# MiniToyRobot.net
KiCad netlist of a schematic drawn in Altium Designer
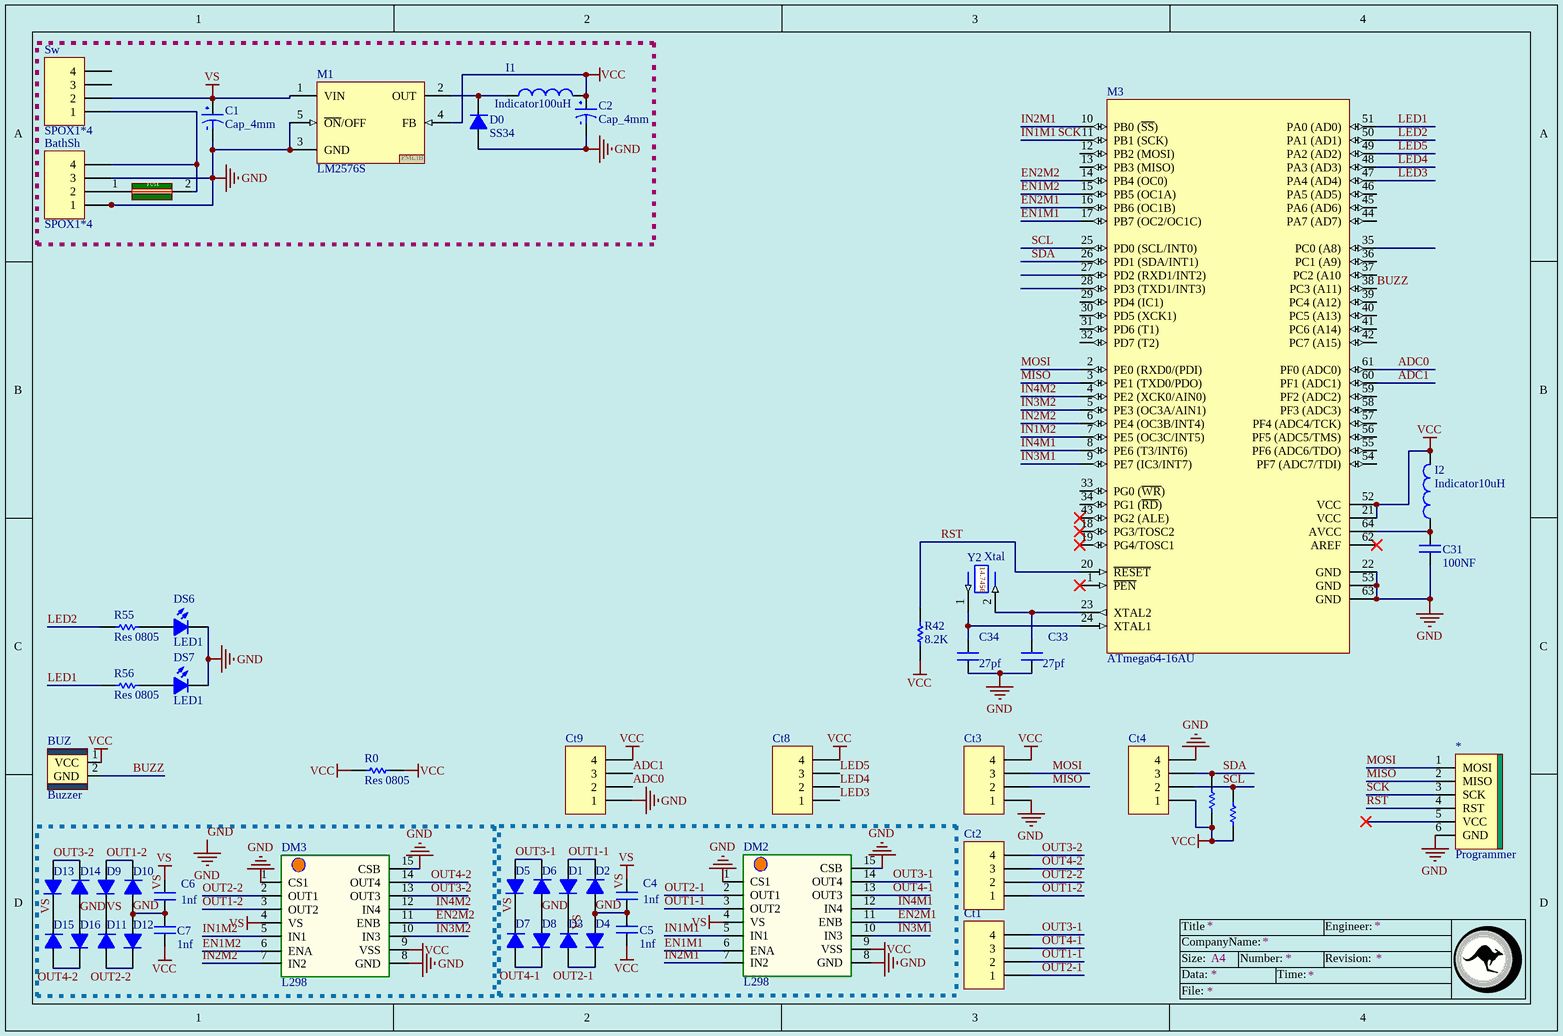
[diagram p0: MiniToyRobot.SchDoc]

(export (version "E")
  (design (tool "Eeschema 10.0.6"))
  (components
    (comp (ref "*")
      (value "Programmer")
      (footprint "Programmer")
      (libsource (lib "PMLIB") (part "Programmer"))
    )
    (comp (ref "BathSh")
      (value "SPOX1*4")
      (footprint "SPOX_1*4RIGHT")
      (libsource (lib "PMLIB") (part "SPOX1*4"))
    )
    (comp (ref "BUZ") (value "Buzzer") (footprint "Buzzer") (libsource (lib "PMLIB") (part "Buzzer")))
    (comp (ref "C1") (value "Cap_4mm") (footprint "Cap_4mm") (libsource (lib "PMLIB") (part "Cap_Pola")))
    (comp (ref "C2") (value "Cap_4mm") (footprint "Cap_4mm") (libsource (lib "PMLIB") (part "Cap_Pola")))
    (comp (ref "C4")
      (value "1nf")
      (footprint "Cap0805")
      (description "surface mount capacitor (size 805)")
      (libsource (lib "PMLIB") (part "Cap0805"))
    )
    (comp (ref "C5")
      (value "1nf")
      (footprint "Cap0805")
      (description "surface mount capacitor (size 805)")
      (libsource (lib "PMLIB") (part "Cap0805"))
    )
    (comp (ref "C6")
      (value "1nf")
      (footprint "Cap0805")
      (description "surface mount capacitor (size 805)")
      (libsource (lib "PMLIB") (part "Cap0805"))
    )
    (comp (ref "C7")
      (value "1nf")
      (footprint "Cap0805")
      (description "surface mount capacitor (size 805)")
      (libsource (lib "PMLIB") (part "Cap0805"))
    )
    (comp (ref "C31")
      (value "100NF")
      (footprint "Cap0805")
      (description "surface mount capacitor (size 805)")
      (libsource (lib "PMLIB") (part "Cap0805"))
    )
    (comp (ref "C33")
      (value "27pf")
      (footprint "Cap0805")
      (description "surface mount capacitor (size 805)")
      (libsource (lib "PMLIB") (part "Cap0805"))
    )
    (comp (ref "C34")
      (value "27pf")
      (footprint "Cap0805")
      (description "surface mount capacitor (size 805)")
      (libsource (lib "PMLIB") (part "Cap0805"))
    )
    (comp (ref "Ct1")
      (value "SPOX1*4")
      (footprint "SPOX_1*4RIGHT")
      (libsource (lib "PMLIB") (part "SPOX1*4"))
    )
    (comp (ref "Ct2")
      (value "SPOX1*4")
      (footprint "SPOX_1*4RIGHT")
      (libsource (lib "PMLIB") (part "SPOX1*4"))
    )
    (comp (ref "Ct3")
      (value "SPOX1*4")
      (footprint "SPOX_1*4RIGHT")
      (libsource (lib "PMLIB") (part "SPOX1*4"))
    )
    (comp (ref "Ct4")
      (value "SPOX1*4")
      (footprint "SPOX_1*4RIGHT")
      (libsource (lib "PMLIB") (part "SPOX1*4"))
    )
    (comp (ref "Ct8")
      (value "SPOX1*4")
      (footprint "SPOX_1*4RIGHT")
      (libsource (lib "PMLIB") (part "SPOX1*4"))
    )
    (comp (ref "Ct9")
      (value "SPOX1*4")
      (footprint "SPOX_1*4RIGHT")
      (libsource (lib "PMLIB") (part "SPOX1*4"))
    )
    (comp (ref "D0") (value "SS34") (footprint "Diod-1A-SMD") (libsource (lib "PMLIB") (part "Diode")))
    (comp (ref "D1") (value "SS14") (footprint "Diod-1A-SMD") (libsource (lib "PMLIB") (part "Diode")))
    (comp (ref "D2") (value "SS14") (footprint "Diod-1A-SMD") (libsource (lib "PMLIB") (part "Diode")))
    (comp (ref "D3") (value "SS14") (footprint "Diod-1A-SMD") (libsource (lib "PMLIB") (part "Diode")))
    (comp (ref "D4") (value "SS14") (footprint "Diod-1A-SMD") (libsource (lib "PMLIB") (part "Diode")))
    (comp (ref "D5") (value "SS14") (footprint "Diod-1A-SMD") (libsource (lib "PMLIB") (part "Diode")))
    (comp (ref "D6") (value "SS14") (footprint "Diod-1A-SMD") (libsource (lib "PMLIB") (part "Diode")))
    (comp (ref "D7") (value "SS14") (footprint "Diod-1A-SMD") (libsource (lib "PMLIB") (part "Diode")))
    (comp (ref "D8") (value "SS14") (footprint "Diod-1A-SMD") (libsource (lib "PMLIB") (part "Diode")))
    (comp (ref "D9") (value "SS14") (footprint "Diod-1A-SMD") (libsource (lib "PMLIB") (part "Diode")))
    (comp (ref "D10") (value "SS14") (footprint "Diod-1A-SMD") (libsource (lib "PMLIB") (part "Diode")))
    (comp (ref "D11") (value "SS14") (footprint "Diod-1A-SMD") (libsource (lib "PMLIB") (part "Diode")))
    (comp (ref "D12") (value "SS14") (footprint "Diod-1A-SMD") (libsource (lib "PMLIB") (part "Diode")))
    (comp (ref "D13") (value "SS14") (footprint "Diod-1A-SMD") (libsource (lib "PMLIB") (part "Diode")))
    (comp (ref "D14") (value "SS14") (footprint "Diod-1A-SMD") (libsource (lib "PMLIB") (part "Diode")))
    (comp (ref "D15") (value "SS14") (footprint "Diod-1A-SMD") (libsource (lib "PMLIB") (part "Diode")))
    (comp (ref "D16") (value "SS14") (footprint "Diod-1A-SMD") (libsource (lib "PMLIB") (part "Diode")))
    (comp (ref "DM2") (value "L298") (footprint "L298") (libsource (lib "PMLIB") (part "L298")))
    (comp (ref "DM3") (value "L298") (footprint "L298") (libsource (lib "PMLIB") (part "L298")))
    (comp (ref "DS6") (value "LED1") (footprint "LED_SMD0805RED") (libsource (lib "PMLIB") (part "LED1")))
    (comp (ref "DS7") (value "LED1") (footprint "LED_SMD0805RED") (libsource (lib "PMLIB") (part "LED1")))
    (comp (ref "Fuse") (value "fuse3") (footprint "fuse_SMD0805") (libsource (lib "PMLIB") (part "fuse3")))
    (comp (ref "I1")
      (value "Indicator100uH")
      (footprint "Indicator_SMD")
      (libsource (lib "PMLIB") (part "Indicator100uH"))
    )
    (comp (ref "I2")
      (value "Indicator10uH")
      (footprint "1206")
      (libsource (lib "PMLIB") (part "Indicator100uH"))
    )
    (comp (ref "M1") (value "LM2576S") (footprint "LM2576S") (libsource (lib "PMLIB") (part "LM2576S")))
    (comp (ref "M3")
      (value "ATmega64-16AU")
      (footprint "64A_N")
      (libsource (lib "Atmel Microcontroller megaAVR") (part "ATmega64-16AU"))
    )
    (comp (ref "R0") (value "Res 0805") (footprint "1206") (libsource (lib "PMLIB") (part "Res 0805")))
    (comp (ref "R42") (value "8.2K") (footprint "R0805") (libsource (lib "PMLIB") (part "Res 0805")))
    (comp (ref "R55") (value "Res 0805") (footprint "R0805") (libsource (lib "PMLIB") (part "Res 0805")))
    (comp (ref "R56") (value "Res 0805") (footprint "R0805") (libsource (lib "PMLIB") (part "Res 0805")))
    (comp (ref "RD1") (value "Res 0805") (footprint "R0805") (libsource (lib "PMLIB") (part "Res 0805")))
    (comp (ref "RD2") (value "Res 0805") (footprint "R0805") (libsource (lib "PMLIB") (part "Res 0805")))
    (comp (ref "Sw") (value "SPOX1*4") (footprint "SPOX_1*4RIGHT") (libsource (lib "PMLIB") (part "SPOX1*4")))
    (comp (ref "Y2") (value "Xtal") (footprint "Crystal") (libsource (lib "PMLIB") (part "Crystal")))
  )
  (nets
    (net (code "1") (name "/ADC0") (class "Default")
      (node (ref "Ct9") (pin "2") (pinfunction "2_2") (pintype "passive"))
      (node (ref "M3") (pin "61") (pinfunction "PF0_(ADC0)_61") (pintype "bidirectional"))
    )
    (net (code "2") (name "/ADC1") (class "Default")
      (node (ref "Ct9") (pin "3") (pinfunction "3_3") (pintype "passive"))
      (node (ref "M3") (pin "60") (pinfunction "PF1_(ADC1)_60") (pintype "bidirectional"))
    )
    (net (code "3") (name "/BUZZ") (class "Default")
      (node (ref "BUZ") (pin "2") (pinfunction "GND_2") (pintype "passive"))
      (node (ref "M3") (pin "38") (pinfunction "PC3_(A11)_38") (pintype "bidirectional"))
    )
    (net (code "4") (name "/EN1M1") (class "Default")
      (node (ref "DM2") (pin "6") (pinfunction "ENA_6") (pintype "passive"))
      (node (ref "M3") (pin "17") (pinfunction "PB7_(OC2/OC1C)_17") (pintype "bidirectional"))
    )
    (net (code "5") (name "/EN1M2") (class "Default")
      (node (ref "DM3") (pin "6") (pinfunction "ENA_6") (pintype "passive"))
      (node (ref "M3") (pin "15") (pinfunction "PB5_(OC1A)_15") (pintype "bidirectional"))
    )
    (net (code "6") (name "/EN2M1") (class "Default")
      (node (ref "DM2") (pin "11") (pinfunction "ENB_11") (pintype "passive"))
      (node (ref "M3") (pin "16") (pinfunction "PB6_(OC1B)_16") (pintype "bidirectional"))
    )
    (net (code "7") (name "/EN2M2") (class "Default")
      (node (ref "DM3") (pin "11") (pinfunction "ENB_11") (pintype "passive"))
      (node (ref "M3") (pin "14") (pinfunction "PB4_(OC0)_14") (pintype "bidirectional"))
    )
    (net (code "8") (name "/IN1M1") (class "Default")
      (node (ref "*") (pin "3") (pinfunction "SCK_3") (pintype "passive"))
      (node (ref "DM2") (pin "5") (pinfunction "IN1_5") (pintype "passive"))
      (node (ref "M3") (pin "11") (pinfunction "PB1_(SCK)_11") (pintype "bidirectional"))
    )
    (net (code "9") (name "/IN1M2") (class "Default")
      (node (ref "DM3") (pin "5") (pinfunction "IN1_5") (pintype "passive"))
      (node (ref "M3") (pin "7") (pinfunction "PE5_(OC3C/INT5)_7") (pintype "bidirectional"))
    )
    (net (code "10") (name "/IN2M1") (class "Default")
      (node (ref "DM2") (pin "7") (pinfunction "IN2_7") (pintype "passive"))
      (node (ref "M3") (pin "10") (pinfunction "PB0_(~{SS})_10") (pintype "bidirectional"))
    )
    (net (code "11") (name "/IN2M2") (class "Default")
      (node (ref "DM3") (pin "7") (pinfunction "IN2_7") (pintype "passive"))
      (node (ref "M3") (pin "6") (pinfunction "PE4_(OC3B/INT4)_6") (pintype "bidirectional"))
    )
    (net (code "12") (name "/IN3M1") (class "Default")
      (node (ref "DM2") (pin "10") (pinfunction "IN3_10") (pintype "passive"))
      (node (ref "M3") (pin "9") (pinfunction "PE7_(IC3/INT7)_9") (pintype "bidirectional"))
    )
    (net (code "13") (name "/IN3M2") (class "Default")
      (node (ref "DM3") (pin "10") (pinfunction "IN3_10") (pintype "passive"))
      (node (ref "M3") (pin "5") (pinfunction "PE3_(OC3A/AIN1)_5") (pintype "bidirectional"))
    )
    (net (code "14") (name "/IN4M1") (class "Default")
      (node (ref "DM2") (pin "12") (pinfunction "IN4_12") (pintype "passive"))
      (node (ref "M3") (pin "8") (pinfunction "PE6_(T3/INT6)_8") (pintype "bidirectional"))
    )
    (net (code "15") (name "/IN4M2") (class "Default")
      (node (ref "DM3") (pin "12") (pinfunction "IN4_12") (pintype "passive"))
      (node (ref "M3") (pin "4") (pinfunction "PE2_(XCK0/AIN0)_4") (pintype "bidirectional"))
    )
    (net (code "16") (name "/LED1") (class "Default")
      (node (ref "M3") (pin "51") (pinfunction "PA0_(AD0)_51") (pintype "bidirectional"))
      (node (ref "R56") (pin "2") (pinfunction "2_2") (pintype "passive"))
    )
    (net (code "17") (name "/LED2") (class "Default")
      (node (ref "M3") (pin "50") (pinfunction "PA1_(AD1)_50") (pintype "bidirectional"))
      (node (ref "R55") (pin "2") (pinfunction "2_2") (pintype "passive"))
    )
    (net (code "18") (name "/LED3") (class "Default")
      (node (ref "Ct8") (pin "1") (pinfunction "1_1") (pintype "passive"))
      (node (ref "M3") (pin "47") (pinfunction "PA4_(AD4)_47") (pintype "bidirectional"))
    )
    (net (code "19") (name "/LED4") (class "Default")
      (node (ref "Ct8") (pin "2") (pinfunction "2_2") (pintype "passive"))
      (node (ref "M3") (pin "48") (pinfunction "PA3_(AD3)_48") (pintype "bidirectional"))
    )
    (net (code "20") (name "/LED5") (class "Default")
      (node (ref "Ct8") (pin "3") (pinfunction "3_3") (pintype "passive"))
      (node (ref "M3") (pin "49") (pinfunction "PA2_(AD2)_49") (pintype "bidirectional"))
    )
    (net (code "21") (name "/MISO") (class "Default")
      (node (ref "*") (pin "2") (pinfunction "MISO_2") (pintype "passive"))
      (node (ref "Ct3") (pin "2") (pinfunction "2_2") (pintype "passive"))
      (node (ref "M3") (pin "3") (pinfunction "PE1_(TXD0/PDO)_3") (pintype "bidirectional"))
    )
    (net (code "22") (name "/MOSI") (class "Default")
      (node (ref "*") (pin "1") (pinfunction "MOSI_1") (pintype "passive"))
      (node (ref "Ct3") (pin "3") (pinfunction "3_3") (pintype "passive"))
      (node (ref "M3") (pin "2") (pinfunction "PE0_(RXD0/(PDI)_2") (pintype "bidirectional"))
    )
    (net (code "23") (name "/OUT1-1") (class "Default")
      (node (ref "Ct1") (pin "2") (pinfunction "2_2") (pintype "passive"))
      (node (ref "D1") (pin "A") (pinfunction "A_A") (pintype "passive"))
      (node (ref "D2") (pin "K") (pinfunction "K_K") (pintype "passive"))
      (node (ref "DM2") (pin "3") (pinfunction "OUT2_3") (pintype "passive"))
    )
    (net (code "24") (name "/OUT1-2") (class "Default")
      (node (ref "Ct2") (pin "1") (pinfunction "1_1") (pintype "passive"))
      (node (ref "D10") (pin "K") (pinfunction "K_K") (pintype "passive"))
      (node (ref "D9") (pin "A") (pinfunction "A_A") (pintype "passive"))
      (node (ref "DM3") (pin "3") (pinfunction "OUT2_3") (pintype "passive"))
    )
    (net (code "25") (name "/OUT2-1") (class "Default")
      (node (ref "Ct1") (pin "1") (pinfunction "1_1") (pintype "passive"))
      (node (ref "D3") (pin "A") (pinfunction "A_A") (pintype "passive"))
      (node (ref "D4") (pin "K") (pinfunction "K_K") (pintype "passive"))
      (node (ref "DM2") (pin "2") (pinfunction "OUT1_2") (pintype "passive"))
    )
    (net (code "26") (name "/OUT2-2") (class "Default")
      (node (ref "Ct2") (pin "2") (pinfunction "2_2") (pintype "passive"))
      (node (ref "D11") (pin "A") (pinfunction "A_A") (pintype "passive"))
      (node (ref "D12") (pin "K") (pinfunction "K_K") (pintype "passive"))
      (node (ref "DM3") (pin "2") (pinfunction "OUT1_2") (pintype "passive"))
    )
    (net (code "27") (name "/OUT3-1") (class "Default")
      (node (ref "Ct1") (pin "4") (pinfunction "4_4") (pintype "passive"))
      (node (ref "D5") (pin "A") (pinfunction "A_A") (pintype "passive"))
      (node (ref "D6") (pin "K") (pinfunction "K_K") (pintype "passive"))
      (node (ref "DM2") (pin "14") (pinfunction "OUT4_14") (pintype "passive"))
    )
    (net (code "28") (name "/OUT3-2") (class "Default")
      (node (ref "Ct2") (pin "4") (pinfunction "4_4") (pintype "passive"))
      (node (ref "D13") (pin "A") (pinfunction "A_A") (pintype "passive"))
      (node (ref "D14") (pin "K") (pinfunction "K_K") (pintype "passive"))
      (node (ref "DM3") (pin "13") (pinfunction "OUT3_13") (pintype "passive"))
    )
    (net (code "29") (name "/OUT4-1") (class "Default")
      (node (ref "Ct1") (pin "3") (pinfunction "3_3") (pintype "passive"))
      (node (ref "D7") (pin "A") (pinfunction "A_A") (pintype "passive"))
      (node (ref "D8") (pin "K") (pinfunction "K_K") (pintype "passive"))
      (node (ref "DM2") (pin "13") (pinfunction "OUT3_13") (pintype "passive"))
    )
    (net (code "30") (name "/OUT4-2") (class "Default")
      (node (ref "Ct2") (pin "3") (pinfunction "3_3") (pintype "passive"))
      (node (ref "D15") (pin "A") (pinfunction "A_A") (pintype "passive"))
      (node (ref "D16") (pin "K") (pinfunction "K_K") (pintype "passive"))
      (node (ref "DM3") (pin "14") (pinfunction "OUT4_14") (pintype "passive"))
    )
    (net (code "31") (name "/RST") (class "Default")
      (node (ref "*") (pin "4") (pinfunction "RST_4") (pintype "passive"))
      (node (ref "M3") (pin "20") (pinfunction "~{RESET}_20") (pintype "input"))
      (node (ref "R42") (pin "1") (pinfunction "1_1") (pintype "passive"))
    )
    (net (code "32") (name "/SCL") (class "Default")
      (node (ref "Ct4") (pin "2") (pinfunction "2_2") (pintype "passive"))
      (node (ref "M3") (pin "25") (pinfunction "PD0_(SCL/INT0)_25") (pintype "bidirectional"))
      (node (ref "RD2") (pin "2") (pinfunction "2_2") (pintype "passive"))
    )
    (net (code "33") (name "/SDA") (class "Default")
      (node (ref "Ct4") (pin "3") (pinfunction "3_3") (pintype "passive"))
      (node (ref "M3") (pin "26") (pinfunction "PD1_(SDA/INT1)_26") (pintype "bidirectional"))
      (node (ref "RD1") (pin "2") (pinfunction "2_2") (pintype "passive"))
    )
    (net (code "34") (name "GND") (class "Default")
      (node (ref "*") (pin "6") (pinfunction "GND_6") (pintype "passive"))
      (node (ref "BathSh") (pin "1") (pinfunction "1_1") (pintype "passive"))
      (node (ref "BathSh") (pin "3") (pinfunction "3_3") (pintype "passive"))
      (node (ref "C1") (pin "1") (pinfunction "1_1") (pintype "passive"))
      (node (ref "C2") (pin "1") (pinfunction "1_1") (pintype "passive"))
      (node (ref "C31") (pin "1") (pinfunction "1_1") (pintype "passive"))
      (node (ref "C33") (pin "1") (pinfunction "1_1") (pintype "passive"))
      (node (ref "C34") (pin "1") (pinfunction "1_1") (pintype "passive"))
      (node (ref "C4") (pin "1") (pinfunction "1_1") (pintype "passive"))
      (node (ref "C5") (pin "2") (pinfunction "2_2") (pintype "passive"))
      (node (ref "C6") (pin "1") (pinfunction "1_1") (pintype "passive"))
      (node (ref "C7") (pin "2") (pinfunction "2_2") (pintype "passive"))
      (node (ref "Ct3") (pin "1") (pinfunction "1_1") (pintype "passive"))
      (node (ref "Ct4") (pin "4") (pinfunction "4_4") (pintype "passive"))
      (node (ref "Ct9") (pin "1") (pinfunction "1_1") (pintype "passive"))
      (node (ref "D0") (pin "A") (pinfunction "A_A") (pintype "passive"))
      (node (ref "D10") (pin "A") (pinfunction "A_A") (pintype "passive"))
      (node (ref "D12") (pin "A") (pinfunction "A_A") (pintype "passive"))
      (node (ref "D14") (pin "A") (pinfunction "A_A") (pintype "passive"))
      (node (ref "D16") (pin "A") (pinfunction "A_A") (pintype "passive"))
      (node (ref "D2") (pin "A") (pinfunction "A_A") (pintype "passive"))
      (node (ref "D4") (pin "A") (pinfunction "A_A") (pintype "passive"))
      (node (ref "D6") (pin "A") (pinfunction "A_A") (pintype "passive"))
      (node (ref "D8") (pin "A") (pinfunction "A_A") (pintype "passive"))
      (node (ref "DM2") (pin "1") (pinfunction "CS1_1") (pintype "passive"))
      (node (ref "DM2") (pin "15") (pinfunction "CSB_15") (pintype "passive"))
      (node (ref "DM2") (pin "8") (pinfunction "GND_8") (pintype "passive"))
      (node (ref "DM3") (pin "1") (pinfunction "CS1_1") (pintype "passive"))
      (node (ref "DM3") (pin "15") (pinfunction "CSB_15") (pintype "passive"))
      (node (ref "DM3") (pin "8") (pinfunction "GND_8") (pintype "passive"))
      (node (ref "DS6") (pin "K") (pinfunction "K_K") (pintype "passive"))
      (node (ref "DS7") (pin "K") (pinfunction "K_K") (pintype "passive"))
      (node (ref "M1") (pin "3") (pinfunction "GND_3") (pintype "power_in"))
      (node (ref "M1") (pin "5") (pinfunction "~{ON}/OFF_5") (pintype "input"))
      (node (ref "M3") (pin "22") (pinfunction "GND_22") (pintype "power_in"))
      (node (ref "M3") (pin "53") (pinfunction "GND_53") (pintype "power_in"))
      (node (ref "M3") (pin "63") (pinfunction "GND_63") (pintype "power_in"))
    )
    (net (code "35") (name "Net-(DS6-PadA)") (class "Default")
      (node (ref "DS6") (pin "A") (pinfunction "A_A") (pintype "passive"))
      (node (ref "R55") (pin "1") (pinfunction "1_1") (pintype "passive"))
    )
    (net (code "36") (name "Net-(DS7-PadA)") (class "Default")
      (node (ref "DS7") (pin "A") (pinfunction "A_A") (pintype "passive"))
      (node (ref "R56") (pin "1") (pinfunction "1_1") (pintype "passive"))
    )
    (net (code "37") (name "Net-(Fuse-IN)") (class "Default")
      (node (ref "BathSh") (pin "2") (pinfunction "2_2") (pintype "passive"))
      (node (ref "Fuse") (pin "1") (pinfunction "IN_1") (pintype "passive"))
    )
    (net (code "38") (name "Net-(Fuse-OUT)") (class "Default")
      (node (ref "BathSh") (pin "4") (pinfunction "4_4") (pintype "passive"))
      (node (ref "Fuse") (pin "2") (pinfunction "OUT_2") (pintype "passive"))
      (node (ref "Sw") (pin "1") (pinfunction "1_1") (pintype "passive"))
    )
    (net (code "39") (name "Net-(M1-OUT)") (class "Default")
      (node (ref "D0") (pin "K") (pinfunction "K_K") (pintype "passive"))
      (node (ref "I1") (pin "1") (pinfunction "1_1") (pintype "passive"))
      (node (ref "M1") (pin "2") (pinfunction "OUT_2") (pintype "power_in"))
    )
    (net (code "40") (name "Net-(M3-AVCC)") (class "Default")
      (node (ref "C31") (pin "2") (pinfunction "2_2") (pintype "passive"))
      (node (ref "I2") (pin "1") (pinfunction "1_1") (pintype "passive"))
      (node (ref "M3") (pin "64") (pinfunction "AVCC_64") (pintype "power_in"))
    )
    (net (code "41") (name "Net-(M3-XTAL1)") (class "Default")
      (node (ref "C34") (pin "2") (pinfunction "2_2") (pintype "passive"))
      (node (ref "M3") (pin "24") (pinfunction "XTAL1_24") (pintype "input"))
      (node (ref "Y2") (pin "1") (pinfunction "1_1") (pintype "output"))
    )
    (net (code "42") (name "Net-(M3-XTAL2)") (class "Default")
      (node (ref "C33") (pin "2") (pinfunction "2_2") (pintype "passive"))
      (node (ref "M3") (pin "23") (pinfunction "XTAL2_23") (pintype "output"))
      (node (ref "Y2") (pin "2") (pinfunction "2_2") (pintype "input"))
    )
    (net (code "43") (name "VCC") (class "Default")
      (node (ref "BUZ") (pin "1") (pinfunction "VCC_1") (pintype "passive"))
      (node (ref "C2") (pin "2") (pinfunction "2_2") (pintype "passive"))
      (node (ref "C5") (pin "1") (pinfunction "1_1") (pintype "passive"))
      (node (ref "C7") (pin "1") (pinfunction "1_1") (pintype "passive"))
      (node (ref "Ct3") (pin "4") (pinfunction "4_4") (pintype "passive"))
      (node (ref "Ct4") (pin "1") (pinfunction "1_1") (pintype "passive"))
      (node (ref "Ct8") (pin "4") (pinfunction "4_4") (pintype "passive"))
      (node (ref "Ct9") (pin "4") (pinfunction "4_4") (pintype "passive"))
      (node (ref "DM2") (pin "9") (pinfunction "VSS_9") (pintype "passive"))
      (node (ref "DM3") (pin "9") (pinfunction "VSS_9") (pintype "passive"))
      (node (ref "I1") (pin "2") (pinfunction "2_2") (pintype "passive"))
      (node (ref "I2") (pin "2") (pinfunction "2_2") (pintype "passive"))
      (node (ref "M1") (pin "4") (pinfunction "FB_4") (pintype "input"))
      (node (ref "M3") (pin "21") (pinfunction "VCC_21") (pintype "power_in"))
      (node (ref "M3") (pin "52") (pinfunction "VCC_52") (pintype "power_in"))
      (node (ref "R0") (pin "1") (pinfunction "1_1") (pintype "passive"))
      (node (ref "R0") (pin "2") (pinfunction "2_2") (pintype "passive"))
      (node (ref "R42") (pin "2") (pinfunction "2_2") (pintype "passive"))
      (node (ref "RD1") (pin "1") (pinfunction "1_1") (pintype "passive"))
      (node (ref "RD2") (pin "1") (pinfunction "1_1") (pintype "passive"))
    )
    (net (code "44") (name "VS") (class "Default")
      (node (ref "C1") (pin "2") (pinfunction "2_2") (pintype "passive"))
      (node (ref "C4") (pin "2") (pinfunction "2_2") (pintype "passive"))
      (node (ref "C6") (pin "2") (pinfunction "2_2") (pintype "passive"))
      (node (ref "D1") (pin "K") (pinfunction "K_K") (pintype "passive"))
      (node (ref "D11") (pin "K") (pinfunction "K_K") (pintype "passive"))
      (node (ref "D13") (pin "K") (pinfunction "K_K") (pintype "passive"))
      (node (ref "D15") (pin "K") (pinfunction "K_K") (pintype "passive"))
      (node (ref "D3") (pin "K") (pinfunction "K_K") (pintype "passive"))
      (node (ref "D5") (pin "K") (pinfunction "K_K") (pintype "passive"))
      (node (ref "D7") (pin "K") (pinfunction "K_K") (pintype "passive"))
      (node (ref "D9") (pin "K") (pinfunction "K_K") (pintype "passive"))
      (node (ref "DM2") (pin "4") (pinfunction "VS_4") (pintype "passive"))
      (node (ref "DM3") (pin "4") (pinfunction "VS_4") (pintype "passive"))
      (node (ref "M1") (pin "1") (pinfunction "VIN_1") (pintype "power_in"))
      (node (ref "Sw") (pin "2") (pinfunction "2_2") (pintype "passive"))
    )
    (net (code "45") (name "unconnected-(*-VCC-Pad5)") (class "Default")
      (node (ref "*") (pin "5") (pinfunction "VCC_5") (pintype "passive+no_connect"))
    )
    (net (code "46") (name "unconnected-(M3-AREF-Pad62)") (class "Default")
      (node (ref "M3") (pin "62") (pinfunction "AREF_62") (pintype "passive+no_connect"))
    )
    (net (code "47") (name "unconnected-(M3-PA5_(AD5)-Pad46)") (class "Default")
      (node (ref "M3") (pin "46") (pinfunction "PA5_(AD5)_46") (pintype "bidirectional"))
    )
    (net (code "48") (name "unconnected-(M3-PA6_(AD6)-Pad45)") (class "Default")
      (node (ref "M3") (pin "45") (pinfunction "PA6_(AD6)_45") (pintype "bidirectional"))
    )
    (net (code "49") (name "unconnected-(M3-PA7_(AD7)-Pad44)") (class "Default")
      (node (ref "M3") (pin "44") (pinfunction "PA7_(AD7)_44") (pintype "bidirectional"))
    )
    (net (code "50") (name "unconnected-(M3-PB2_(MOSI)-Pad12)") (class "Default")
      (node (ref "M3") (pin "12") (pinfunction "PB2_(MOSI)_12") (pintype "bidirectional"))
    )
    (net (code "51") (name "unconnected-(M3-PB3_(MISO)-Pad13)") (class "Default")
      (node (ref "M3") (pin "13") (pinfunction "PB3_(MISO)_13") (pintype "bidirectional"))
    )
    (net (code "52") (name "unconnected-(M3-PC0_(A8)-Pad35)") (class "Default")
      (node (ref "M3") (pin "35") (pinfunction "PC0_(A8)_35") (pintype "bidirectional"))
    )
    (net (code "53") (name "unconnected-(M3-PC1_(A9)-Pad36)") (class "Default")
      (node (ref "M3") (pin "36") (pinfunction "PC1_(A9)_36") (pintype "bidirectional"))
    )
    (net (code "54") (name "unconnected-(M3-PC2_(A10-Pad37)") (class "Default")
      (node (ref "M3") (pin "37") (pinfunction "PC2_(A10_37") (pintype "bidirectional"))
    )
    (net (code "55") (name "unconnected-(M3-PC4_(A12)-Pad39)") (class "Default")
      (node (ref "M3") (pin "39") (pinfunction "PC4_(A12)_39") (pintype "bidirectional"))
    )
    (net (code "56") (name "unconnected-(M3-PC5_(A13)-Pad40)") (class "Default")
      (node (ref "M3") (pin "40") (pinfunction "PC5_(A13)_40") (pintype "bidirectional"))
    )
    (net (code "57") (name "unconnected-(M3-PC6_(A14)-Pad41)") (class "Default")
      (node (ref "M3") (pin "41") (pinfunction "PC6_(A14)_41") (pintype "bidirectional"))
    )
    (net (code "58") (name "unconnected-(M3-PC7_(A15)-Pad42)") (class "Default")
      (node (ref "M3") (pin "42") (pinfunction "PC7_(A15)_42") (pintype "bidirectional"))
    )
    (net (code "59") (name "unconnected-(M3-PD2_(RXD1{slash}INT2)-Pad27)") (class "Default")
      (node (ref "M3") (pin "27") (pinfunction "PD2_(RXD1/INT2)_27") (pintype "bidirectional"))
    )
    (net (code "60") (name "unconnected-(M3-PD3_(TXD1{slash}INT3)-Pad28)") (class "Default")
      (node (ref "M3") (pin "28") (pinfunction "PD3_(TXD1/INT3)_28") (pintype "bidirectional"))
    )
    (net (code "61") (name "unconnected-(M3-PD4_(IC1)-Pad29)") (class "Default")
      (node (ref "M3") (pin "29") (pinfunction "PD4_(IC1)_29") (pintype "bidirectional"))
    )
    (net (code "62") (name "unconnected-(M3-PD5_(XCK1)-Pad30)") (class "Default")
      (node (ref "M3") (pin "30") (pinfunction "PD5_(XCK1)_30") (pintype "bidirectional"))
    )
    (net (code "63") (name "unconnected-(M3-PD6_(T1)-Pad31)") (class "Default")
      (node (ref "M3") (pin "31") (pinfunction "PD6_(T1)_31") (pintype "bidirectional"))
    )
    (net (code "64") (name "unconnected-(M3-PD7_(T2)-Pad32)") (class "Default")
      (node (ref "M3") (pin "32") (pinfunction "PD7_(T2)_32") (pintype "bidirectional"))
    )
    (net (code "65") (name "unconnected-(M3-PF2_(ADC2)-Pad59)") (class "Default")
      (node (ref "M3") (pin "59") (pinfunction "PF2_(ADC2)_59") (pintype "bidirectional"))
    )
    (net (code "66") (name "unconnected-(M3-PF3_(ADC3)-Pad58)") (class "Default")
      (node (ref "M3") (pin "58") (pinfunction "PF3_(ADC3)_58") (pintype "bidirectional"))
    )
    (net (code "67") (name "unconnected-(M3-PF4_(ADC4{slash}TCK)-Pad57)") (class "Default")
      (node (ref "M3") (pin "57") (pinfunction "PF4_(ADC4/TCK)_57") (pintype "bidirectional"))
    )
    (net (code "68") (name "unconnected-(M3-PF5_(ADC5{slash}TMS)-Pad56)") (class "Default")
      (node (ref "M3") (pin "56") (pinfunction "PF5_(ADC5/TMS)_56") (pintype "bidirectional"))
    )
    (net (code "69") (name "unconnected-(M3-PF6_(ADC6{slash}TDO)-Pad55)") (class "Default")
      (node (ref "M3") (pin "55") (pinfunction "PF6_(ADC6/TDO)_55") (pintype "bidirectional"))
    )
    (net (code "70") (name "unconnected-(M3-PF7_(ADC7{slash}TDI)-Pad54)") (class "Default")
      (node (ref "M3") (pin "54") (pinfunction "PF7_(ADC7/TDI)_54") (pintype "bidirectional"))
    )
    (net (code "71") (name "unconnected-(M3-PG0_(~{WR})-Pad33)") (class "Default")
      (node (ref "M3") (pin "33") (pinfunction "PG0_(~{WR})_33") (pintype "bidirectional"))
    )
    (net (code "72") (name "unconnected-(M3-PG1_(~{RD})-Pad34)") (class "Default")
      (node (ref "M3") (pin "34") (pinfunction "PG1_(~{RD})_34") (pintype "bidirectional"))
    )
    (net (code "73") (name "unconnected-(M3-PG2_(ALE)-Pad43)") (class "Default")
      (node (ref "M3") (pin "43") (pinfunction "PG2_(ALE)_43") (pintype "bidirectional+no_connect"))
    )
    (net (code "74") (name "unconnected-(M3-PG3{slash}TOSC2-Pad18)") (class "Default")
      (node (ref "M3") (pin "18") (pinfunction "PG3/TOSC2_18") (pintype "bidirectional+no_connect"))
    )
    (net (code "75") (name "unconnected-(M3-PG4{slash}TOSC1-Pad19)") (class "Default")
      (node (ref "M3") (pin "19") (pinfunction "PG4/TOSC1_19") (pintype "bidirectional+no_connect"))
    )
    (net (code "76") (name "unconnected-(M3-~{PEN}-Pad1)") (class "Default")
      (node (ref "M3") (pin "1") (pinfunction "~{PEN}_1") (pintype "input+no_connect"))
    )
    (net (code "77") (name "unconnected-(Sw-Pad3)") (class "Default")
      (node (ref "Sw") (pin "3") (pinfunction "3_3") (pintype "passive"))
    )
    (net (code "78") (name "unconnected-(Sw-Pad4)") (class "Default")
      (node (ref "Sw") (pin "4") (pinfunction "4_4") (pintype "passive"))
    )
  )
)
